# PhotonButtons.net
KiCad netlist of a schematic drawn in EAGLE
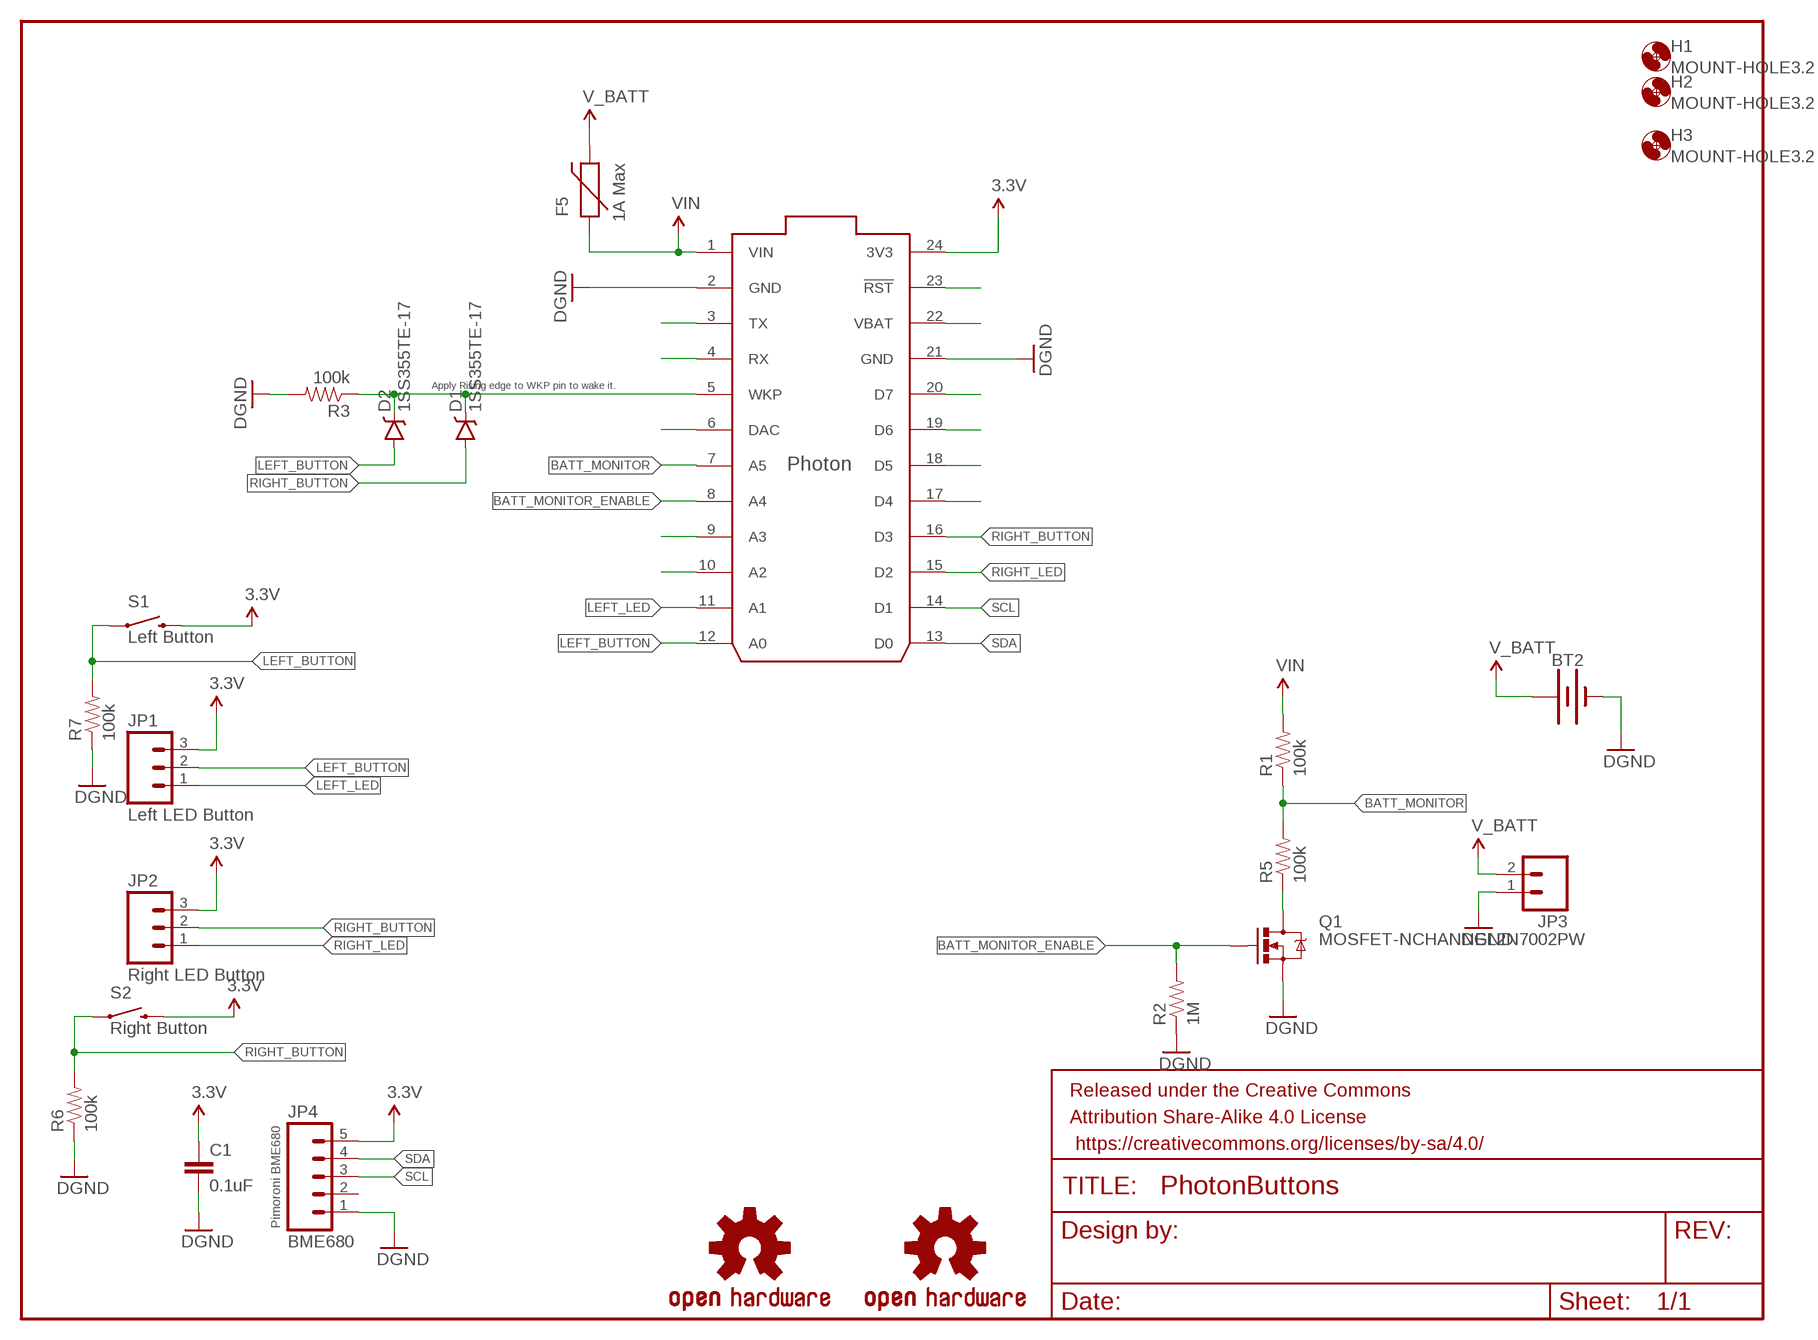
[diagram p0: schematic, sheet 1]

(export (version "E")
  (design (tool "Eeschema 10.0.6"))
  (components
    (comp (ref "BT2")
      (value "BATTERY-16340")
      (footprint "eagle-import:BATTERY_16340-HOLDER")
      (libsource (lib "eagle-import") (part "BATTERY-16340"))
    )
    (comp (ref "C1")
      (value "0.1uF")
      (footprint "eagle-import:0805")
      (libsource (lib "eagle-import") (part "CAP0805"))
    )
    (comp (ref "D1")
      (value "1SS355TE-17")
      (footprint "eagle-import:SOD-323")
      (libsource (lib "eagle-import") (part "DIODE-SCHOTTKY-BAT20J"))
    )
    (comp (ref "D2")
      (value "1SS355TE-17")
      (footprint "eagle-import:SOD-323")
      (libsource (lib "eagle-import") (part "DIODE-SCHOTTKY-BAT20J"))
    )
    (comp (ref "F5")
      (value "1A Max")
      (footprint "eagle-import:PTC-1206")
      (libsource (lib "eagle-import") (part "PTCTHERMISTOR1206"))
    )
    (comp (ref "FRAME1")
      (value "FRAME-LETTER")
      (footprint "eagle-import:CREATIVE_COMMONS")
      (libsource (lib "eagle-import") (part "FRAME-LETTER"))
    )
    (comp (ref "H1")
      (value "MOUNT-HOLE3.2")
      (footprint "eagle-import:3,2")
      (libsource (lib "eagle-import") (part "MOUNT-HOLE3.2"))
    )
    (comp (ref "H2")
      (value "MOUNT-HOLE3.2")
      (footprint "eagle-import:3,2")
      (libsource (lib "eagle-import") (part "MOUNT-HOLE3.2"))
    )
    (comp (ref "H3")
      (value "MOUNT-HOLE3.2")
      (footprint "eagle-import:3,2")
      (libsource (lib "eagle-import") (part "MOUNT-HOLE3.2"))
    )
    (comp (ref "JP1")
      (value "Left LED Button")
      (footprint "eagle-import:MOLEX-1X3")
      (libsource (lib "eagle-import") (part "M03POLAR"))
    )
    (comp (ref "JP2")
      (value "Right LED Button")
      (footprint "eagle-import:MOLEX-1X3")
      (libsource (lib "eagle-import") (part "M03POLAR"))
    )
    (comp (ref "JP3")
      (value "M02-JST-2MM-SMT")
      (footprint "eagle-import:JST-2-SMD")
      (libsource (lib "eagle-import") (part "M02-JST-2MM-SMT"))
    )
    (comp (ref "JP4")
      (value "BME680")
      (footprint "eagle-import:1X05")
      (libsource (lib "eagle-import") (part "M05PTH"))
    )
    (comp (ref "LOGO1")
      (value "OSHW-LOGOL")
      (footprint "eagle-import:OSHW-LOGO-L")
      (libsource (lib "eagle-import") (part "OSHW-LOGOL"))
    )
    (comp (ref "LOGO2")
      (value "OSHW-LOGOL")
      (footprint "eagle-import:OSHW-LOGO-L")
      (libsource (lib "eagle-import") (part "OSHW-LOGOL"))
    )
    (comp (ref "Q1")
      (value "MOSFET-NCHANNEL2N7002PW")
      (footprint "eagle-import:SOT323")
      (libsource (lib "eagle-import") (part "MOSFET-NCHANNEL2N7002PW"))
    )
    (comp (ref "R1")
      (value "100k")
      (footprint "eagle-import:0805")
      (libsource (lib "eagle-import") (part "RESISTOR0805-RES"))
    )
    (comp (ref "R2")
      (value "1M")
      (footprint "eagle-import:0805")
      (libsource (lib "eagle-import") (part "RESISTOR0805-RES"))
    )
    (comp (ref "R3")
      (value "100k")
      (footprint "eagle-import:0805")
      (libsource (lib "eagle-import") (part "RESISTOR0805-RES"))
    )
    (comp (ref "R5")
      (value "100k")
      (footprint "eagle-import:0805")
      (libsource (lib "eagle-import") (part "RESISTOR0805-RES"))
    )
    (comp (ref "R6")
      (value "100k")
      (footprint "eagle-import:0805")
      (libsource (lib "eagle-import") (part "RESISTOR0805-RES"))
    )
    (comp (ref "R7")
      (value "100k")
      (footprint "eagle-import:0805")
      (libsource (lib "eagle-import") (part "RESISTOR0805-RES"))
    )
    (comp (ref "S1")
      (value "Left Button")
      (footprint "eagle-import:TACTILE-PTH")
      (libsource (lib "eagle-import") (part "SWITCH-MOMENTARY-2PTH"))
    )
    (comp (ref "S2")
      (value "Right Button")
      (footprint "eagle-import:TACTILE-PTH")
      (libsource (lib "eagle-import") (part "SWITCH-MOMENTARY-2PTH"))
    )
    (comp (ref "U$1")
      (value "PHOTON_SMD")
      (footprint "eagle-import:PHOTON_SMD")
      (libsource (lib "eagle-import") (part "PHOTON_SMD"))
    )
  )
  (nets
    (net (code "1") (name "3.3V") (class "Default")
      (node (ref "C1") (pin "1") (pinfunction "1_1") (pintype "passive"))
      (node (ref "JP1") (pin "3") (pinfunction "3_3") (pintype "passive"))
      (node (ref "JP2") (pin "3") (pinfunction "3_3") (pintype "passive"))
      (node (ref "JP4") (pin "5") (pinfunction "5_5") (pintype "passive"))
      (node (ref "S1") (pin "3") (pinfunction "2_3") (pintype "passive"))
      (node (ref "S2") (pin "3") (pinfunction "2_3") (pintype "passive"))
      (node (ref "U$1") (pin "24") (pinfunction "3V3_24") (pintype "power_in"))
    )
    (net (code "2") (name "BATT_MONITOR") (class "Default")
      (node (ref "R1") (pin "1") (pinfunction "1_1") (pintype "passive"))
      (node (ref "R5") (pin "2") (pinfunction "2_2") (pintype "passive"))
      (node (ref "U$1") (pin "7") (pinfunction "A5_7") (pintype "bidirectional"))
    )
    (net (code "3") (name "BATT_MONITOR_ENABLE") (class "Default")
      (node (ref "Q1") (pin "1") (pinfunction "G_1") (pintype "passive"))
      (node (ref "R2") (pin "2") (pinfunction "2_2") (pintype "passive"))
      (node (ref "U$1") (pin "8") (pinfunction "A4_8") (pintype "bidirectional"))
    )
    (net (code "4") (name "DGND") (class "Default")
      (node (ref "BT2") (pin "P$2") (pinfunction "-_P$2") (pintype "power_in"))
      (node (ref "C1") (pin "2") (pinfunction "2_2") (pintype "passive"))
      (node (ref "JP3") (pin "1") (pinfunction "2_1") (pintype "passive"))
      (node (ref "JP4") (pin "1") (pinfunction "1_1") (pintype "passive"))
      (node (ref "Q1") (pin "2") (pinfunction "S_2") (pintype "passive"))
      (node (ref "R2") (pin "1") (pinfunction "1_1") (pintype "passive"))
      (node (ref "R3") (pin "2") (pinfunction "2_2") (pintype "passive"))
      (node (ref "R6") (pin "1") (pinfunction "1_1") (pintype "passive"))
      (node (ref "R7") (pin "1") (pinfunction "1_1") (pintype "passive"))
      (node (ref "U$1") (pin "2") (pinfunction "GND_2") (pintype "power_in"))
      (node (ref "U$1") (pin "21") (pinfunction "GND_21") (pintype "power_in"))
    )
    (net (code "5") (name "LEFT_BUTTON") (class "Default")
      (node (ref "D2") (pin "A") (pinfunction "A_A") (pintype "passive"))
      (node (ref "JP1") (pin "2") (pinfunction "2_2") (pintype "passive"))
      (node (ref "R7") (pin "2") (pinfunction "2_2") (pintype "passive"))
      (node (ref "S1") (pin "1") (pinfunction "1_1") (pintype "passive"))
      (node (ref "U$1") (pin "12") (pinfunction "A0_12") (pintype "bidirectional"))
    )
    (net (code "6") (name "LEFT_LED") (class "Default")
      (node (ref "JP1") (pin "1") (pinfunction "1_1") (pintype "passive"))
      (node (ref "U$1") (pin "11") (pinfunction "A1_11") (pintype "bidirectional"))
    )
    (net (code "7") (name "Net-(Q1-D)") (class "Default")
      (node (ref "Q1") (pin "3") (pinfunction "D_3") (pintype "passive"))
      (node (ref "R5") (pin "1") (pinfunction "1_1") (pintype "passive"))
    )
    (net (code "8") (name "Net-(U$1A-WKP)") (class "Default")
      (node (ref "D1") (pin "C") (pinfunction "C_C") (pintype "passive"))
      (node (ref "D2") (pin "C") (pinfunction "C_C") (pintype "passive"))
      (node (ref "R3") (pin "1") (pinfunction "1_1") (pintype "passive"))
      (node (ref "U$1") (pin "5") (pinfunction "WKP_5") (pintype "bidirectional"))
    )
    (net (code "9") (name "RIGHT_BUTTON") (class "Default")
      (node (ref "D1") (pin "A") (pinfunction "A_A") (pintype "passive"))
      (node (ref "JP2") (pin "2") (pinfunction "2_2") (pintype "passive"))
      (node (ref "R6") (pin "2") (pinfunction "2_2") (pintype "passive"))
      (node (ref "S2") (pin "1") (pinfunction "1_1") (pintype "passive"))
      (node (ref "U$1") (pin "16") (pinfunction "D3_16") (pintype "bidirectional"))
    )
    (net (code "10") (name "RIGHT_LED") (class "Default")
      (node (ref "JP2") (pin "1") (pinfunction "1_1") (pintype "passive"))
      (node (ref "U$1") (pin "15") (pinfunction "D2_15") (pintype "bidirectional"))
    )
    (net (code "11") (name "SCL") (class "Default")
      (node (ref "JP4") (pin "3") (pinfunction "3_3") (pintype "passive"))
      (node (ref "U$1") (pin "14") (pinfunction "D1_14") (pintype "bidirectional"))
    )
    (net (code "12") (name "SDA") (class "Default")
      (node (ref "JP4") (pin "4") (pinfunction "4_4") (pintype "passive"))
      (node (ref "U$1") (pin "13") (pinfunction "D0_13") (pintype "bidirectional"))
    )
    (net (code "13") (name "VIN") (class "Default")
      (node (ref "F5") (pin "1") (pinfunction "1_1") (pintype "bidirectional"))
      (node (ref "R1") (pin "2") (pinfunction "2_2") (pintype "passive"))
      (node (ref "U$1") (pin "1") (pinfunction "VIN_1") (pintype "power_in"))
    )
    (net (code "14") (name "V_BATT") (class "Default")
      (node (ref "BT2") (pin "P$1") (pinfunction "+_P$1") (pintype "power_in"))
      (node (ref "F5") (pin "2") (pinfunction "2_2") (pintype "bidirectional"))
      (node (ref "JP3") (pin "2") (pinfunction "1_2") (pintype "passive"))
    )
    (net (code "15") (name "unconnected-(JP4-Pad2)") (class "Default")
      (node (ref "JP4") (pin "2") (pinfunction "2_2") (pintype "passive"))
    )
    (net (code "16") (name "unconnected-(U$1A-A2-Pad10)") (class "Default")
      (node (ref "U$1") (pin "10") (pinfunction "A2_10") (pintype "bidirectional"))
    )
    (net (code "17") (name "unconnected-(U$1A-A3-Pad9)") (class "Default")
      (node (ref "U$1") (pin "9") (pinfunction "A3_9") (pintype "bidirectional"))
    )
    (net (code "18") (name "unconnected-(U$1A-D4-Pad17)") (class "Default")
      (node (ref "U$1") (pin "17") (pinfunction "D4_17") (pintype "bidirectional"))
    )
    (net (code "19") (name "unconnected-(U$1A-D5-Pad18)") (class "Default")
      (node (ref "U$1") (pin "18") (pinfunction "D5_18") (pintype "bidirectional"))
    )
    (net (code "20") (name "unconnected-(U$1A-D6-Pad19)") (class "Default")
      (node (ref "U$1") (pin "19") (pinfunction "D6_19") (pintype "bidirectional"))
    )
    (net (code "21") (name "unconnected-(U$1A-D7-Pad20)") (class "Default")
      (node (ref "U$1") (pin "20") (pinfunction "D7_20") (pintype "bidirectional"))
    )
    (net (code "22") (name "unconnected-(U$1A-DAC-Pad6)") (class "Default")
      (node (ref "U$1") (pin "6") (pinfunction "DAC_6") (pintype "bidirectional"))
    )
    (net (code "23") (name "unconnected-(U$1A-RX-Pad4)") (class "Default")
      (node (ref "U$1") (pin "4") (pinfunction "RX_4") (pintype "bidirectional"))
    )
    (net (code "24") (name "unconnected-(U$1A-TX-Pad3)") (class "Default")
      (node (ref "U$1") (pin "3") (pinfunction "TX_3") (pintype "bidirectional"))
    )
    (net (code "25") (name "unconnected-(U$1A-VBAT-Pad22)") (class "Default")
      (node (ref "U$1") (pin "22") (pinfunction "VBAT_22") (pintype "power_in"))
    )
    (net (code "26") (name "unconnected-(U$1A-~{RST}-Pad23)") (class "Default")
      (node (ref "U$1") (pin "23") (pinfunction "~{RST}_23") (pintype "bidirectional"))
    )
  )
)
